# receiver_SCH.net
KiCad netlist of a schematic drawn in Altium Designer
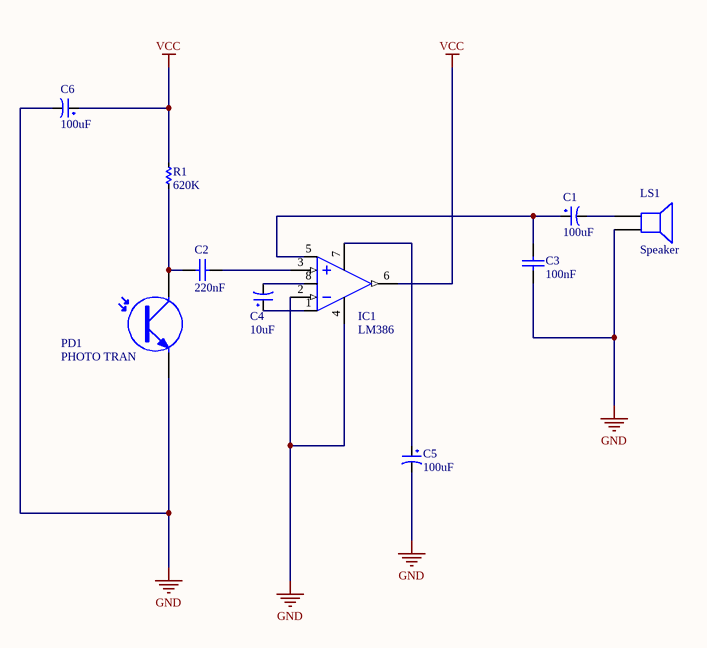
[diagram p0: receiver_SCH.SchDoc]

(export (version "E")
  (design (tool "Eeschema 10.0.6"))
  (components
    (comp (ref "C1")
      (value "100uF")
      (footprint "tu hoa 5mm")
      (description "Cắm")
      (libsource (lib "") (part "Tu Hoa 100uF 25V 6x11_1"))
    )
    (comp (ref "C2")
      (value "220nF")
      (footprint "CN1.5")
      (description "Capacitor")
      (fields (field (name "Comment") "Cap Non-Pol"))
      (libsource (lib "TechMT.VN_Lib_Project v1.0") (part "Cap Non-Pol"))
    )
    (comp (ref "C3")
      (value "100nF")
      (footprint "CN1.5")
      (description "Capacitor")
      (fields (field (name "Comment") "Cap Non-Pol"))
      (libsource (lib "TechMT.VN_Lib_Project v1.0") (part "Cap Non-Pol"))
    )
    (comp (ref "C4")
      (value "10uF")
      (footprint "tu hoa 4mm")
      (description "Cắm")
      (libsource (lib "THU VIEN SCH") (part "Tu Hoa 10uF 25V 4x7"))
    )
    (comp (ref "C5")
      (value "100uF")
      (footprint "tu hoa 5mm")
      (description "Cắm")
      (libsource (lib "THU VIEN SCH") (part "Tu Hoa 100uF 25V 6x11"))
    )
    (comp (ref "C6")
      (value "100uF")
      (footprint "tu hoa 5mm")
      (description "Cắm")
      (libsource (lib "") (part "Tu Hoa 100uF 25V 6x11_1"))
    )
    (comp (ref "IC1")
      (value "LM386")
      (footprint "DIP8")
      (description "Low-Power Dual Operational Amplifier")
      (libsource (lib "TechMT.VN_Lib_Project v2") (part "LM386"))
    )
    (comp (ref "LS1")
      (value "Speaker")
      (footprint "SP1")
      (description "Loudspeaker")
      (fields (field (name "PUBLISHER") "Altium Limited"))
      (libsource (lib "Devzone_SCHLib") (part "Speaker"))
    )
    (comp (ref "PD1")
      (value "PHOTO TRAN")
      (footprint "LED-5TRED")
      (description "Photo TRAN")
      (fields (field (name "PUBLISHER") "Altium Limited"))
      (libsource (lib "Devzone_SCHLib") (part "Photo TRAN"))
    )
    (comp (ref "R1")
      (value "620K")
      (footprint "RES-2W")
      (description "Res")
      (fields
        (field (name "MANUFACTURER") "Generic Components")
        (field (name "PUBLISHER") "Altium Hobart Technology Centre")
      )
      (libsource (lib "TechMT.VN_Lib_Project v2") (part "Res"))
    )
  )
  (nets
    (net (code "1") (name "GND") (class "Default")
      (node (ref "C3") (pin "2") (pinfunction "2_2") (pintype "passive"))
      (node (ref "C5") (pin "2") (pinfunction "2_2") (pintype "passive"))
      (node (ref "C6") (pin "2") (pinfunction "2_2") (pintype "passive"))
      (node (ref "IC1") (pin "2") (pinfunction "IN-_2") (pintype "input"))
      (node (ref "IC1") (pin "4") (pinfunction "-V_4") (pintype "passive"))
      (node (ref "LS1") (pin "2") (pinfunction "2_2") (pintype "passive"))
      (node (ref "PD1") (pin "2") (pinfunction "E_2") (pintype "passive"))
    )
    (net (code "2") (name "Net-(C1-Pad1)") (class "Default")
      (node (ref "C1") (pin "1") (pinfunction "1_1") (pintype "passive"))
      (node (ref "C3") (pin "1") (pinfunction "1_1") (pintype "passive"))
      (node (ref "IC1") (pin "5") (pinfunction "-V_5") (pintype "passive"))
    )
    (net (code "3") (name "Net-(C1-Pad2)") (class "Default")
      (node (ref "C1") (pin "2") (pinfunction "2_2") (pintype "passive"))
      (node (ref "LS1") (pin "1") (pinfunction "1_1") (pintype "passive"))
    )
    (net (code "4") (name "Net-(C4-Pad1)") (class "Default")
      (node (ref "C4") (pin "1") (pinfunction "1_1") (pintype "passive"))
      (node (ref "IC1") (pin "1") (pinfunction "-V_1") (pintype "passive"))
    )
    (net (code "5") (name "Net-(C4-Pad2)") (class "Default")
      (node (ref "C4") (pin "2") (pinfunction "2_2") (pintype "passive"))
      (node (ref "IC1") (pin "8") (pinfunction "-V_8") (pintype "passive"))
    )
    (net (code "6") (name "Net-(IC1-+V)") (class "Default")
      (node (ref "C5") (pin "1") (pinfunction "1_1") (pintype "passive"))
      (node (ref "IC1") (pin "7") (pinfunction "+V_7") (pintype "passive"))
    )
    (net (code "7") (name "Net-(IC1-IN+)") (class "Default")
      (node (ref "C2") (pin "2") (pinfunction "2_2") (pintype "passive"))
      (node (ref "IC1") (pin "3") (pinfunction "IN+_3") (pintype "input"))
    )
    (net (code "8") (name "Net-(PD1-C)") (class "Default")
      (node (ref "C2") (pin "1") (pinfunction "1_1") (pintype "passive"))
      (node (ref "PD1") (pin "1") (pinfunction "C_1") (pintype "passive"))
      (node (ref "R1") (pin "2") (pinfunction "2_2") (pintype "passive"))
    )
    (net (code "9") (name "VCC") (class "Default")
      (node (ref "C6") (pin "1") (pinfunction "1_1") (pintype "passive"))
      (node (ref "IC1") (pin "6") (pinfunction "OUT_6") (pintype "output"))
      (node (ref "R1") (pin "1") (pinfunction "1_1") (pintype "passive"))
    )
  )
)
